# MSXIV_BatteryModuleConnectorBoard.net
KiCad netlist of a schematic drawn in Altium Designer
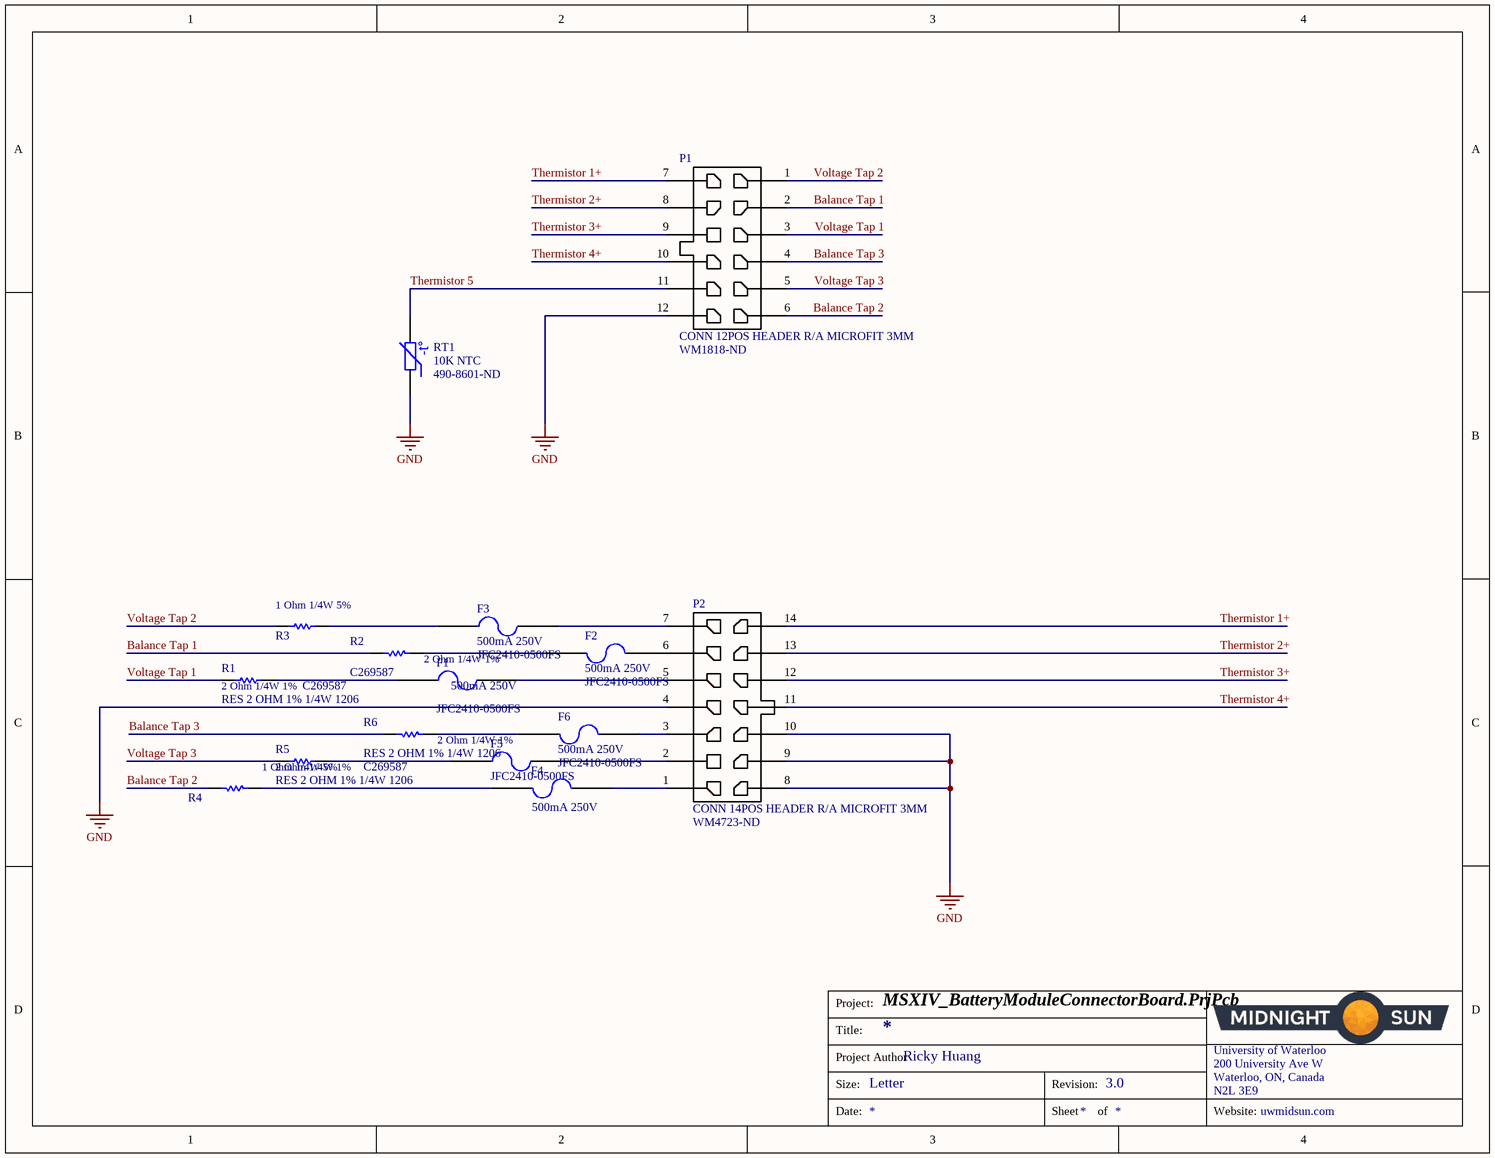
[diagram p0: MSXIV_BatteryModuleConnectorBoard.SchDoc]

(export (version "E")
  (design (tool "Eeschema 10.0.6"))
  (components
    (comp (ref "F1")
      (value "500mA 250V")
      (footprint "FUSE JFC2410-0500FS")
      (description "2410 Surface Mount Fuses RoHS")
      (fields (field (name "MANUFACTURER PART NUMBER 1") "JFC2410-0500FS"))
      (libsource (lib "Schematic Diagrams") (part "FUSE 500MA LCSC"))
    )
    (comp (ref "F2")
      (value "500mA 250V")
      (footprint "FUSE JFC2410-0500FS")
      (description "2410 Surface Mount Fuses RoHS")
      (fields (field (name "MANUFACTURER PART NUMBER 1") "JFC2410-0500FS"))
      (libsource (lib "") (part "FUSE 500MA LCSC_1"))
    )
    (comp (ref "F3")
      (value "500mA 250V")
      (footprint "FUSE JFC2410-0500FS")
      (description "2410 Surface Mount Fuses RoHS")
      (fields (field (name "MANUFACTURER PART NUMBER 1") "JFC2410-0500FS"))
      (libsource (lib "Schematic Diagrams") (part "FUSE 500MA LCSC"))
    )
    (comp (ref "F4")
      (value "500mA 250V")
      (footprint "FUSE JFC2410-0500FS")
      (description "2410 Surface Mount Fuses RoHS")
      (libsource (lib "") (part "FUSE 500MA LCSC_1"))
    )
    (comp (ref "F5")
      (value "500mA 250V")
      (footprint "FUSE JFC2410-0500FS")
      (description "2410 Surface Mount Fuses RoHS")
      (fields (field (name "MANUFACTURER PART NUMBER 1") "JFC2410-0500FS"))
      (libsource (lib "Schematic Diagrams") (part "FUSE 500MA LCSC"))
    )
    (comp (ref "F6")
      (value "500mA 250V")
      (footprint "FUSE JFC2410-0500FS")
      (description "2410 Surface Mount Fuses RoHS")
      (fields (field (name "MANUFACTURER PART NUMBER 1") "JFC2410-0500FS"))
      (libsource (lib "") (part "FUSE 500MA LCSC_1"))
    )
    (comp (ref "P1")
      (value "CONN 12POS HEADER R/A MICROFIT 3MM")
      (footprint "CONN, 12POS 3MM HEADER R/A")
      (fields (field (name "SUPPLIER PART NUMBER 1") "WM1818-ND"))
      (libsource (lib "Schematic Diagrams") (part "CONN 12POS HEADER R/A MICROFIT 3MM"))
    )
    (comp (ref "P2")
      (value "CONN 14POS HEADER R/A MICROFIT 3MM")
      (footprint "CONN, 14POS 3MM HEADER R/A")
      (fields (field (name "SUPPLIER PART NUMBER 1") "WM4723-ND"))
      (libsource (lib "Schematic Diagrams") (part "CONN 14POS HEADER R/A MICROFIT 3MM"))
    )
    (comp (ref "R1")
      (value "RES 2 OHM 1% 1/4W 1206")
      (footprint "RES 1206")
      (description "2 ±1% 1/4W 1206 Chip Resistor - Surface Mount RoHS")
      (fields (field (name "SUPPLIER PART NUMBER 1") "C269587"))
      (libsource (lib "Schematic Diagrams") (part "RES 2 OHM 1% 1/4W 1206"))
    )
    (comp (ref "R2")
      (value "RES 2 OHM 1% 1/4W 1206")
      (footprint "RES 1206")
      (description "2 ±1% 1/4W 1206 Chip Resistor - Surface Mount RoHS")
      (fields (field (name "SUPPLIER PART NUMBER 1") "C269587"))
      (libsource (lib "Schematic Diagrams") (part "RES 2 OHM 1% 1/4W 1206"))
    )
    (comp (ref "R3")
      (value "RES 1 OHM 5% 1/4W 1206")
      (footprint "RES 1206")
      (description "1 ±5% 1/4W 1206 Chip Resistor - Surface Mount RoHS")
      (libsource (lib "Schematic Diagrams") (part "RES 1 OHM 5% 1/4W 1206"))
    )
    (comp (ref "R4")
      (value "RES 1 OHM 5% 1/4W 1206")
      (footprint "RES 1206")
      (description "1 ±5% 1/4W 1206 Chip Resistor - Surface Mount RoHS")
      (libsource (lib "Schematic Diagrams") (part "RES 1 OHM 5% 1/4W 1206"))
    )
    (comp (ref "R5")
      (value "RES 2 OHM 1% 1/4W 1206")
      (footprint "RES 1206")
      (description "2 ±1% 1/4W 1206 Chip Resistor - Surface Mount RoHS")
      (libsource (lib "Schematic Diagrams") (part "RES 2 OHM 1% 1/4W 1206"))
    )
    (comp (ref "R6")
      (value "RES 2 OHM 1% 1/4W 1206")
      (footprint "RES 1206")
      (description "2 ±1% 1/4W 1206 Chip Resistor - Surface Mount RoHS")
      (fields (field (name "SUPPLIER PART NUMBER 1") "C269587"))
      (libsource (lib "Schematic Diagrams") (part "RES 2 OHM 1% 1/4W 1206"))
    )
    (comp (ref "RT1")
      (value "10K NTC")
      (footprint "NTC THERMISTOR BEAD")
      (description "NTC Thermistor 10k Bead")
      (fields
        (field (name "MANUFACTURER") "Murata Electronics North America")
        (field (name "MANUFACTURER PART NUMBER") "NXRT15XH103FA1B030")
        (field (name "SUPPLIER PART NUMBER 1") "490-8601-ND")
      )
      (libsource (lib "Schematic Diagrams") (part "NTC THERMISTOR 10K 1% BEAD"))
    )
  )
  (nets
    (net (code "1") (name "/Balance Tap 1") (class "Default")
      (node (ref "P1") (pin "2") (pinfunction "2_2") (pintype "passive"))
      (node (ref "R2") (pin "2") (pinfunction "2_2") (pintype "passive"))
    )
    (net (code "2") (name "/Balance Tap 2") (class "Default")
      (node (ref "P1") (pin "6") (pinfunction "6_6") (pintype "passive"))
      (node (ref "R4") (pin "2") (pinfunction "2_2") (pintype "passive"))
    )
    (net (code "3") (name "/Balance Tap 3") (class "Default")
      (node (ref "P1") (pin "4") (pinfunction "4_4") (pintype "passive"))
      (node (ref "R6") (pin "2") (pinfunction "2_2") (pintype "passive"))
    )
    (net (code "4") (name "/Thermistor 1+") (class "Default")
      (node (ref "P1") (pin "7") (pinfunction "7_7") (pintype "passive"))
      (node (ref "P2") (pin "14") (pinfunction "14_14") (pintype "passive"))
    )
    (net (code "5") (name "/Thermistor 2+") (class "Default")
      (node (ref "P1") (pin "8") (pinfunction "8_8") (pintype "passive"))
      (node (ref "P2") (pin "13") (pinfunction "13_13") (pintype "passive"))
    )
    (net (code "6") (name "/Thermistor 3+") (class "Default")
      (node (ref "P1") (pin "9") (pinfunction "9_9") (pintype "passive"))
      (node (ref "P2") (pin "12") (pinfunction "12_12") (pintype "passive"))
    )
    (net (code "7") (name "/Thermistor 4+") (class "Default")
      (node (ref "P1") (pin "10") (pinfunction "10_10") (pintype "passive"))
      (node (ref "P2") (pin "11") (pinfunction "11_11") (pintype "passive"))
    )
    (net (code "8") (name "/Thermistor 5") (class "Default")
      (node (ref "P1") (pin "11") (pinfunction "11_11") (pintype "passive"))
      (node (ref "RT1") (pin "2") (pinfunction "2_2") (pintype "passive"))
    )
    (net (code "9") (name "/Voltage Tap 1") (class "Default")
      (node (ref "P1") (pin "3") (pinfunction "3_3") (pintype "passive"))
      (node (ref "R1") (pin "1") (pinfunction "1_1") (pintype "passive"))
    )
    (net (code "10") (name "/Voltage Tap 2") (class "Default")
      (node (ref "P1") (pin "1") (pinfunction "1_1") (pintype "passive"))
      (node (ref "R3") (pin "1") (pinfunction "1_1") (pintype "passive"))
    )
    (net (code "11") (name "/Voltage Tap 3") (class "Default")
      (node (ref "P1") (pin "5") (pinfunction "5_5") (pintype "passive"))
      (node (ref "R5") (pin "1") (pinfunction "1_1") (pintype "passive"))
    )
    (net (code "12") (name "GND") (class "Default")
      (node (ref "P1") (pin "12") (pinfunction "12_12") (pintype "passive"))
      (node (ref "P2") (pin "10") (pinfunction "10_10") (pintype "passive"))
      (node (ref "P2") (pin "4") (pinfunction "4_4") (pintype "passive"))
      (node (ref "P2") (pin "8") (pinfunction "8_8") (pintype "passive"))
      (node (ref "P2") (pin "9") (pinfunction "9_9") (pintype "passive"))
      (node (ref "RT1") (pin "1") (pinfunction "1_1") (pintype "passive"))
    )
    (net (code "13") (name "Net-(F1-Pad1)") (class "Default")
      (node (ref "F1") (pin "1") (pinfunction "1_1") (pintype "passive"))
      (node (ref "R1") (pin "2") (pinfunction "2_2") (pintype "passive"))
    )
    (net (code "14") (name "Net-(F1-Pad2)") (class "Default")
      (node (ref "F1") (pin "2") (pinfunction "2_2") (pintype "passive"))
      (node (ref "P2") (pin "5") (pinfunction "5_5") (pintype "passive"))
    )
    (net (code "15") (name "Net-(F2-Pad1)") (class "Default")
      (node (ref "F2") (pin "1") (pinfunction "1_1") (pintype "passive"))
      (node (ref "P2") (pin "6") (pinfunction "6_6") (pintype "passive"))
    )
    (net (code "16") (name "Net-(F2-Pad2)") (class "Default")
      (node (ref "F2") (pin "2") (pinfunction "2_2") (pintype "passive"))
      (node (ref "R2") (pin "1") (pinfunction "1_1") (pintype "passive"))
    )
    (net (code "17") (name "Net-(F3-Pad1)") (class "Default")
      (node (ref "F3") (pin "1") (pinfunction "1_1") (pintype "passive"))
      (node (ref "R3") (pin "2") (pinfunction "2_2") (pintype "passive"))
    )
    (net (code "18") (name "Net-(F3-Pad2)") (class "Default")
      (node (ref "F3") (pin "2") (pinfunction "2_2") (pintype "passive"))
      (node (ref "P2") (pin "7") (pinfunction "7_7") (pintype "passive"))
    )
    (net (code "19") (name "Net-(F4-Pad1)") (class "Default")
      (node (ref "F4") (pin "1") (pinfunction "1_1") (pintype "passive"))
      (node (ref "P2") (pin "1") (pinfunction "1_1") (pintype "passive"))
    )
    (net (code "20") (name "Net-(F4-Pad2)") (class "Default")
      (node (ref "F4") (pin "2") (pinfunction "2_2") (pintype "passive"))
      (node (ref "R4") (pin "1") (pinfunction "1_1") (pintype "passive"))
    )
    (net (code "21") (name "Net-(F5-Pad1)") (class "Default")
      (node (ref "F5") (pin "1") (pinfunction "1_1") (pintype "passive"))
      (node (ref "R5") (pin "2") (pinfunction "2_2") (pintype "passive"))
    )
    (net (code "22") (name "Net-(F5-Pad2)") (class "Default")
      (node (ref "F5") (pin "2") (pinfunction "2_2") (pintype "passive"))
      (node (ref "P2") (pin "2") (pinfunction "2_2") (pintype "passive"))
    )
    (net (code "23") (name "Net-(F6-Pad1)") (class "Default")
      (node (ref "F6") (pin "1") (pinfunction "1_1") (pintype "passive"))
      (node (ref "P2") (pin "3") (pinfunction "3_3") (pintype "passive"))
    )
    (net (code "24") (name "Net-(F6-Pad2)") (class "Default")
      (node (ref "F6") (pin "2") (pinfunction "2_2") (pintype "passive"))
      (node (ref "R6") (pin "1") (pinfunction "1_1") (pintype "passive"))
    )
  )
)
